# sensor.net
KiCad netlist of a schematic drawn in EAGLE
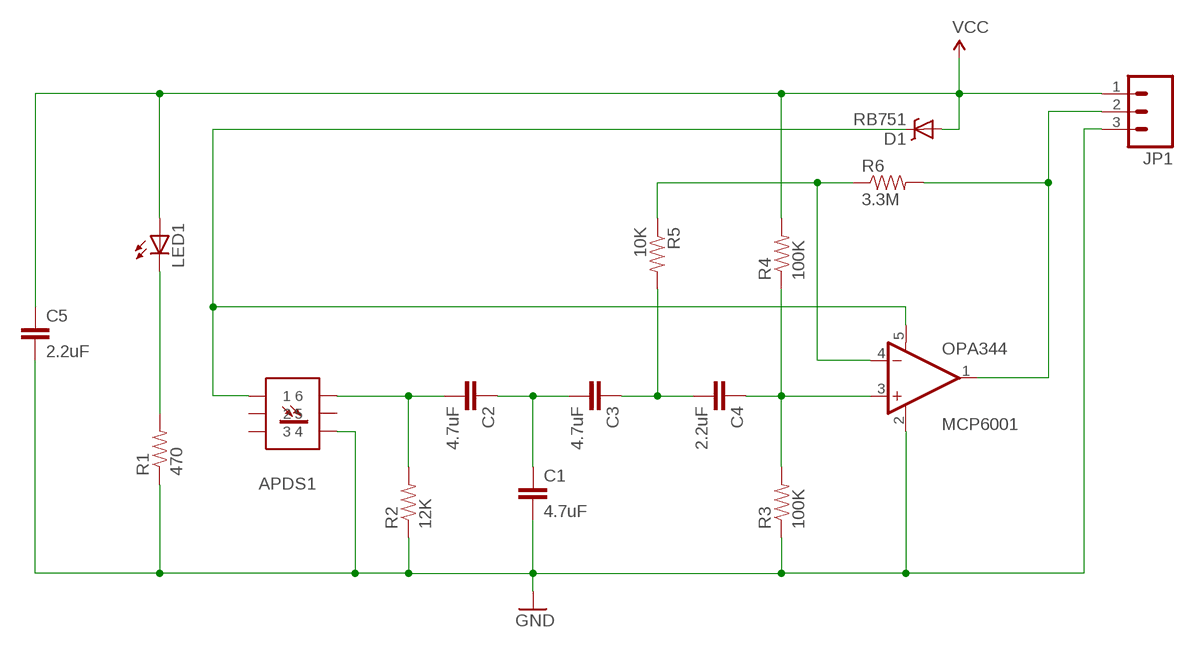
[diagram p0: schematic, sheet 1]

(export (version "E")
  (design (tool "Eeschema 10.0.6"))
  (components
    (comp (ref "APDS1")
      (value "APDS-9008")
      (footprint "eagle-import:MINIATURE-CHIPLED")
      (libsource (lib "eagle-import") (part "APDS-9008"))
    )
    (comp (ref "C1")
      (value "4.7uF")
      (footprint "eagle-import:0603-CAP")
      (libsource (lib "eagle-import") (part "1.0UF-16V-10%(0603)"))
    )
    (comp (ref "C2")
      (value "4.7uF")
      (footprint "eagle-import:0603-CAP")
      (libsource (lib "eagle-import") (part "1.0UF-16V-10%(0603)"))
    )
    (comp (ref "C3")
      (value "4.7uF")
      (footprint "eagle-import:0603-CAP")
      (libsource (lib "eagle-import") (part "1.0UF-16V-10%(0603)"))
    )
    (comp (ref "C4")
      (value "2.2uF")
      (footprint "eagle-import:0603-CAP")
      (fields (field (name "PROD_ID") "CAP-00868"))
      (libsource (lib "eagle-import") (part "1.0UF-16V-10%(0603)"))
    )
    (comp (ref "C5")
      (value "2.2uF")
      (footprint "eagle-import:0603-CAP")
      (fields (field (name "PROD_ID") "CAP-00868"))
      (libsource (lib "eagle-import") (part "1.0UF-16V-10%(0603)"))
    )
    (comp (ref "D1")
      (value "RB751")
      (footprint "eagle-import:SOD-523")
      (libsource (lib "eagle-import") (part "RB751"))
    )
    (comp (ref "JP1")
      (value "M03LONGPADS")
      (footprint "eagle-import:1X03_LONGPADS")
      (libsource (lib "eagle-import") (part "M03LONGPADS"))
    )
    (comp (ref "LED1")
      (value "LED0603")
      (footprint "eagle-import:LED-0603")
      (libsource (lib "eagle-import") (part "LED0603"))
    )
    (comp (ref "MCP6001")
      (value "OPA344")
      (footprint "eagle-import:SOT23-5")
      (libsource (lib "eagle-import") (part "OPA344"))
    )
    (comp (ref "R1")
      (value "470")
      (footprint "eagle-import:0603-RES")
      (libsource (lib "eagle-import") (part "10KOHM1/10W1%(0603)0603"))
    )
    (comp (ref "R2")
      (value "12K")
      (footprint "eagle-import:0603-RES")
      (libsource (lib "eagle-import") (part "10KOHM1/10W1%(0603)0603"))
    )
    (comp (ref "R3")
      (value "100K")
      (footprint "eagle-import:0603-RES")
      (libsource (lib "eagle-import") (part "10KOHM1/10W1%(0603)0603"))
    )
    (comp (ref "R4")
      (value "100K")
      (footprint "eagle-import:0603-RES")
      (libsource (lib "eagle-import") (part "10KOHM1/10W1%(0603)0603"))
    )
    (comp (ref "R5")
      (value "10K")
      (footprint "eagle-import:0603-RES")
      (libsource (lib "eagle-import") (part "10KOHM1/10W1%(0603)0603"))
    )
    (comp (ref "R6")
      (value "3.3M")
      (footprint "eagle-import:0603-RES")
      (fields (field (name "PROD_ID") "RES-00824"))
      (libsource (lib "eagle-import") (part "10KOHM1/10W1%(0603)0603"))
    )
  )
  (nets
    (net (code "1") (name "GND") (class "Default")
      (node (ref "APDS1") (pin "P$4") (pinfunction "4_P$4") (pintype "passive"))
      (node (ref "C1") (pin "2") (pinfunction "2_2") (pintype "passive"))
      (node (ref "C5") (pin "2") (pinfunction "2_2") (pintype "passive"))
      (node (ref "JP1") (pin "3") (pinfunction "3_3") (pintype "passive"))
      (node (ref "MCP6001") (pin "2") (pinfunction "V-_2") (pintype "power_in"))
      (node (ref "R1") (pin "1") (pinfunction "1_1") (pintype "passive"))
      (node (ref "R2") (pin "1") (pinfunction "1_1") (pintype "passive"))
      (node (ref "R3") (pin "1") (pinfunction "1_1") (pintype "passive"))
    )
    (net (code "2") (name "Net-(APDS1-1)") (class "Default")
      (node (ref "APDS1") (pin "P$1") (pinfunction "1_P$1") (pintype "passive"))
      (node (ref "D1") (pin "C") (pinfunction "C_C") (pintype "passive"))
      (node (ref "MCP6001") (pin "5") (pinfunction "V+_5") (pintype "power_in"))
    )
    (net (code "3") (name "Net-(APDS1-6)") (class "Default")
      (node (ref "APDS1") (pin "P$6") (pinfunction "6_P$6") (pintype "passive"))
      (node (ref "C2") (pin "2") (pinfunction "2_2") (pintype "passive"))
      (node (ref "R2") (pin "2") (pinfunction "2_2") (pintype "passive"))
    )
    (net (code "4") (name "Net-(C1-Pad1)") (class "Default")
      (node (ref "C1") (pin "1") (pinfunction "1_1") (pintype "passive"))
      (node (ref "C2") (pin "1") (pinfunction "1_1") (pintype "passive"))
      (node (ref "C3") (pin "2") (pinfunction "2_2") (pintype "passive"))
    )
    (net (code "5") (name "Net-(C3-Pad1)") (class "Default")
      (node (ref "C3") (pin "1") (pinfunction "1_1") (pintype "passive"))
      (node (ref "C4") (pin "2") (pinfunction "2_2") (pintype "passive"))
      (node (ref "R5") (pin "2") (pinfunction "2_2") (pintype "passive"))
    )
    (net (code "6") (name "Net-(LED1-PadC)") (class "Default")
      (node (ref "LED1") (pin "C") (pinfunction "C_C") (pintype "passive"))
      (node (ref "R1") (pin "2") (pinfunction "2_2") (pintype "passive"))
    )
    (net (code "7") (name "Net-(MCP6001-+IN)") (class "Default")
      (node (ref "C4") (pin "1") (pinfunction "1_1") (pintype "passive"))
      (node (ref "MCP6001") (pin "3") (pinfunction "+IN_3") (pintype "input"))
      (node (ref "R3") (pin "2") (pinfunction "2_2") (pintype "passive"))
      (node (ref "R4") (pin "1") (pinfunction "1_1") (pintype "passive"))
    )
    (net (code "8") (name "Net-(MCP6001--IN)") (class "Default")
      (node (ref "MCP6001") (pin "4") (pinfunction "-IN_4") (pintype "input"))
      (node (ref "R5") (pin "1") (pinfunction "1_1") (pintype "passive"))
      (node (ref "R6") (pin "1") (pinfunction "1_1") (pintype "passive"))
    )
    (net (code "9") (name "Net-(MCP6001-OUT)") (class "Default")
      (node (ref "JP1") (pin "2") (pinfunction "2_2") (pintype "passive"))
      (node (ref "MCP6001") (pin "1") (pinfunction "OUT_1") (pintype "output"))
      (node (ref "R6") (pin "2") (pinfunction "2_2") (pintype "passive"))
    )
    (net (code "10") (name "VCC") (class "Default")
      (node (ref "C5") (pin "1") (pinfunction "1_1") (pintype "passive"))
      (node (ref "D1") (pin "A") (pinfunction "A_A") (pintype "passive"))
      (node (ref "JP1") (pin "1") (pinfunction "1_1") (pintype "passive"))
      (node (ref "LED1") (pin "A") (pinfunction "A_A") (pintype "passive"))
      (node (ref "R4") (pin "2") (pinfunction "2_2") (pintype "passive"))
    )
    (net (code "11") (name "unconnected-(APDS1-2-PadP$2)") (class "Default")
      (node (ref "APDS1") (pin "P$2") (pinfunction "2_P$2") (pintype "passive"))
    )
    (net (code "12") (name "unconnected-(APDS1-3-PadP$3)") (class "Default")
      (node (ref "APDS1") (pin "P$3") (pinfunction "3_P$3") (pintype "passive"))
    )
    (net (code "13") (name "unconnected-(APDS1-5-PadP$5)") (class "Default")
      (node (ref "APDS1") (pin "P$5") (pinfunction "5_P$5") (pintype "passive"))
    )
  )
)
